# USB_Serial.net
KiCad netlist of a schematic drawn in Altium Designer
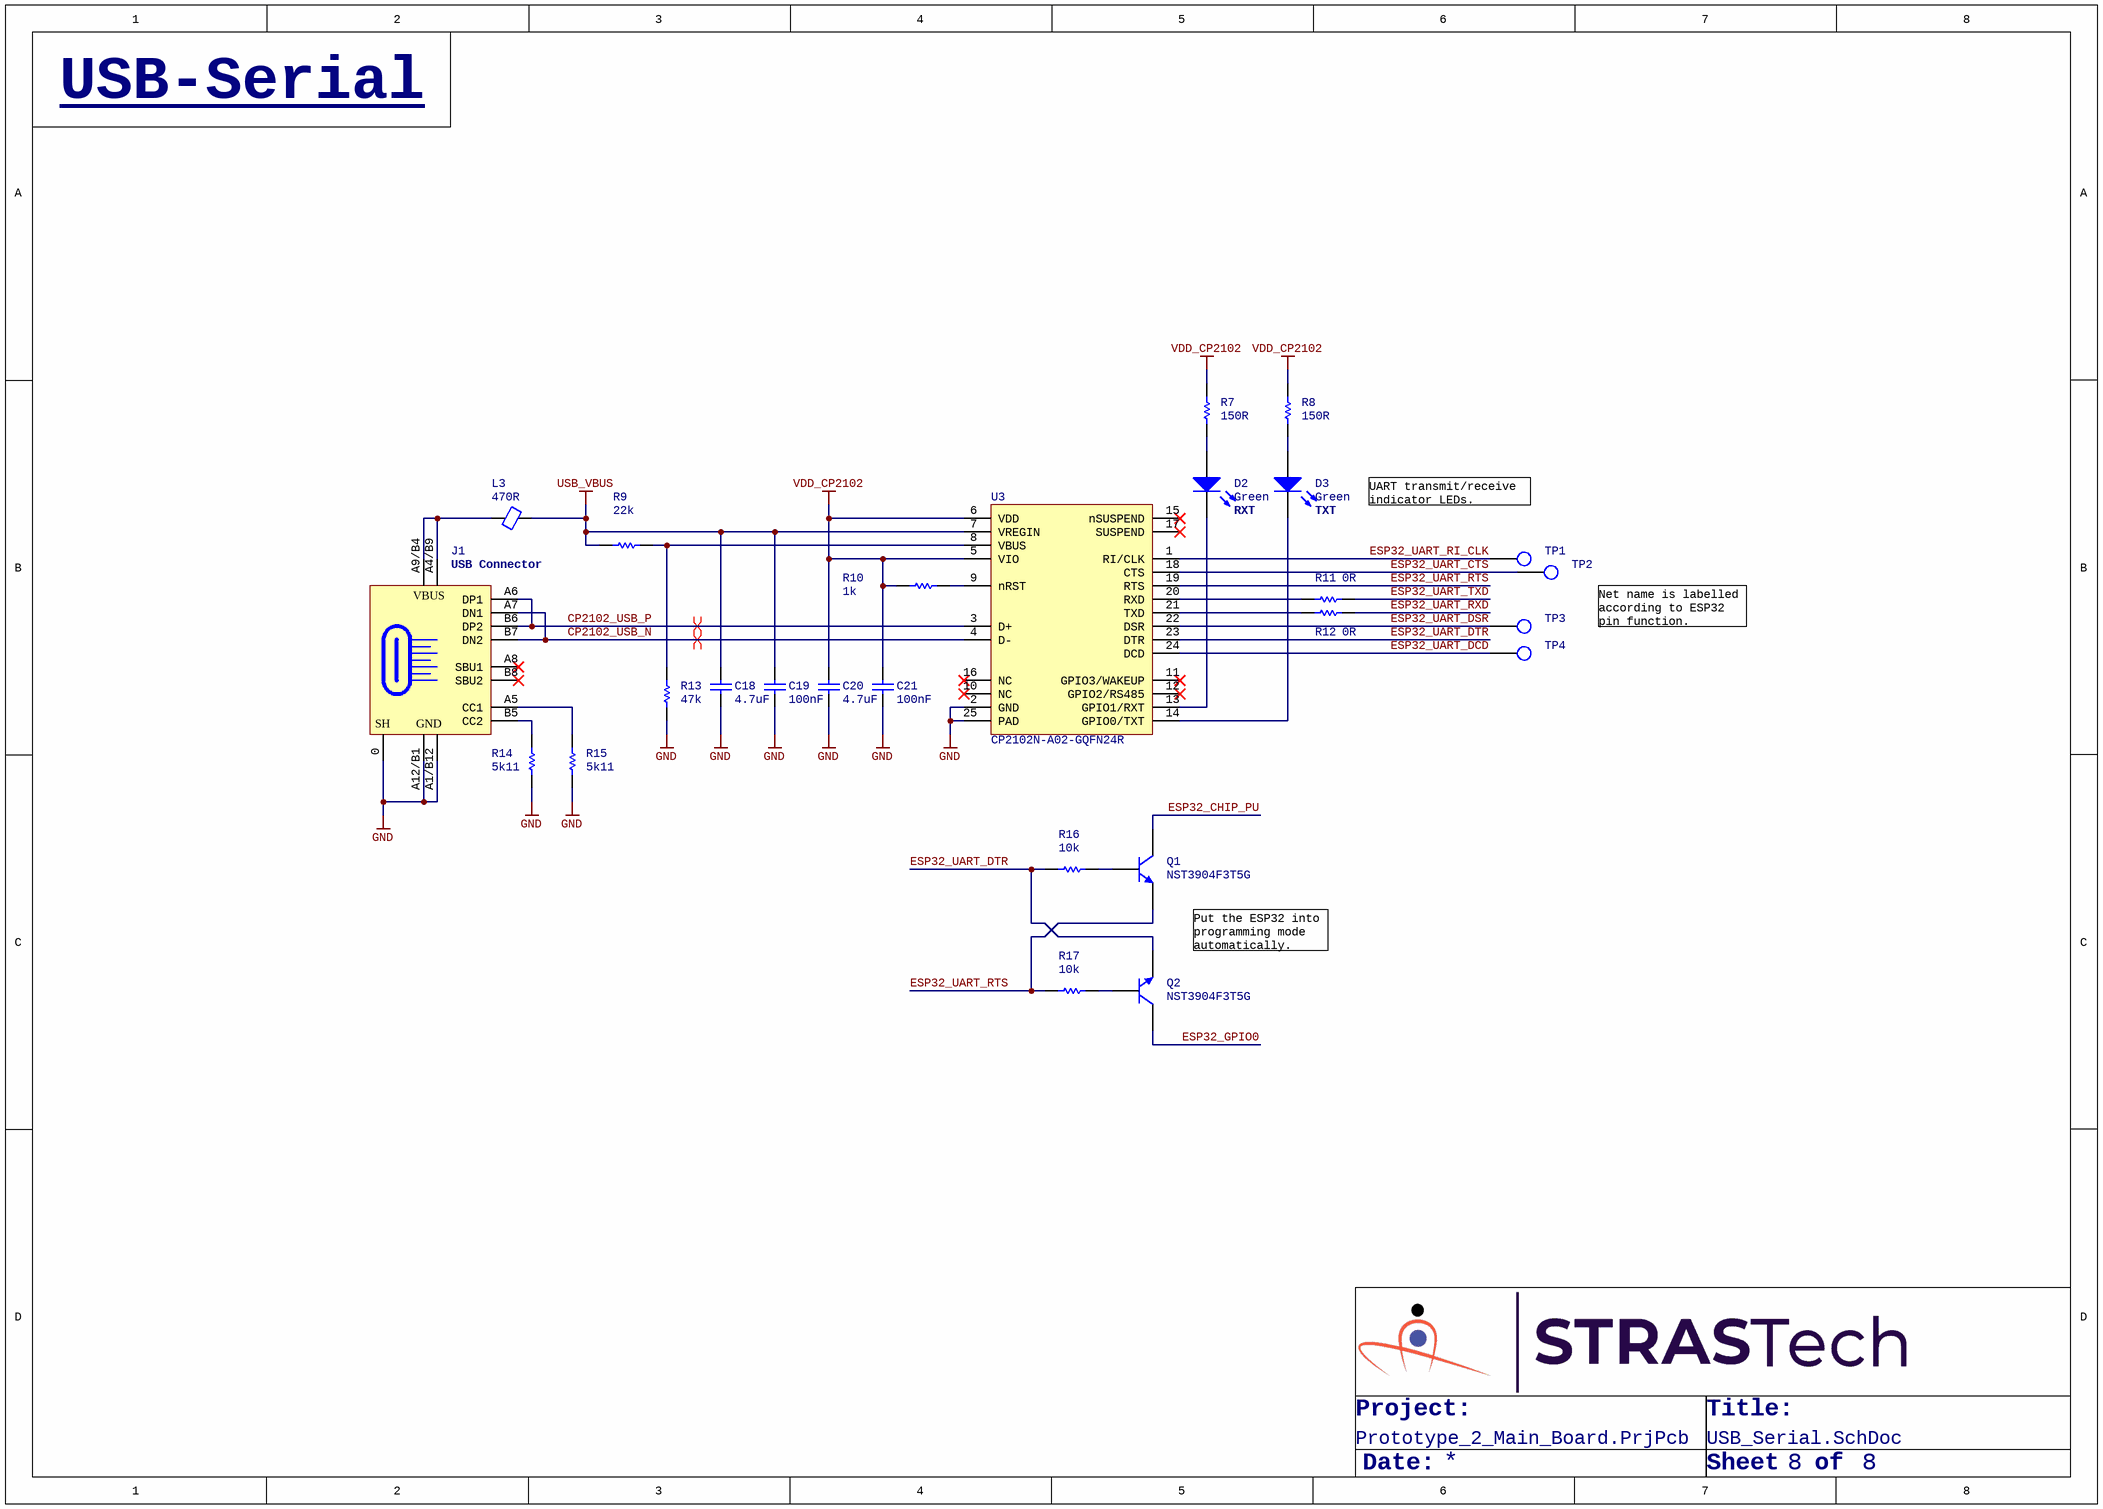
[diagram p0: USB_Serial.SchDoc]

(export (version "E")
  (design (tool "Eeschema 10.0.6"))
  (components
    (comp (ref "C18")
      (value "4.7uF")
      (footprint "Cap,SMD,0402")
      (description "4.7 µF ±20% 16V Ceramic Capacitor X5R 0402 (1005 Metric)")
      (fields
        (field (name "VENDOR PART NUMBER") "478-10788-1-ND")
        (field (name "MANUFACTURER") "AVX Corporation")
        (field (name "CREATEDBY") "Judd Foster")
      )
      (libsource (lib "symbols") (part "CAP,Cer,4.7uF,16VDC,X5R,0402"))
    )
    (comp (ref "C19")
      (value "100nF")
      (footprint "Cap,SMD,0402")
      (description "0.1µF ±10% 25V Ceramic Capacitor X7R 0402 (1005 Metric)")
      (fields
        (field (name "VENDOR PART NUMBER") "490-14603-1-ND")
        (field (name "MANUFACTURER") "Murata Electronics")
        (field (name "CREATEDBY") "Judd Foster")
      )
      (libsource (lib "symbols") (part "CAP,Cer,100nF,25VDC,X7R,0402"))
    )
    (comp (ref "C20")
      (value "4.7uF")
      (footprint "Cap,SMD,0402")
      (description "4.7 µF ±20% 16V Ceramic Capacitor X5R 0402 (1005 Metric)")
      (fields
        (field (name "VENDOR PART NUMBER") "478-10788-1-ND")
        (field (name "MANUFACTURER") "AVX Corporation")
        (field (name "CREATEDBY") "Judd Foster")
      )
      (libsource (lib "symbols") (part "CAP,Cer,4.7uF,16VDC,X5R,0402"))
    )
    (comp (ref "C21")
      (value "100nF")
      (footprint "Cap,SMD,0402")
      (description "0.1µF ±10% 25V Ceramic Capacitor X7R 0402 (1005 Metric)")
      (fields
        (field (name "VENDOR PART NUMBER") "490-14603-1-ND")
        (field (name "MANUFACTURER") "Murata Electronics")
        (field (name "CREATEDBY") "Judd Foster")
      )
      (libsource (lib "symbols") (part "CAP,Cer,100nF,25VDC,X7R,0402"))
    )
    (comp (ref "D2")
      (value "Green")
      (footprint "LED,0603")
      (description "Green 530nm LED Indication - Discrete 3V 0603 (1608 Metric)")
      (fields
        (field (name "MANUFACTURER") "Stanley Electric Co")
        (field (name "MANUFACTURER PART NUMBER") "THG1111C-0005-TR")
        (field (name "CREATEDBY") "Judd Foster")
      )
      (libsource (lib "symbols") (part "LED,Green,SMD,0603"))
    )
    (comp (ref "D3")
      (value "Green")
      (footprint "LED,0603")
      (description "Green 530nm LED Indication - Discrete 3V 0603 (1608 Metric)")
      (fields
        (field (name "MANUFACTURER") "Stanley Electric Co")
        (field (name "MANUFACTURER PART NUMBER") "THG1111C-0005-TR")
        (field (name "CREATEDBY") "Judd Foster")
      )
      (libsource (lib "symbols") (part "LED,Green,SMD,0603"))
    )
    (comp (ref "J1")
      (value "USB")
      (footprint "CONN,USB_C,SMD")
      (fields
        (field (name "MANUFACTURER") "GCT")
        (field (name "MANUFACTURER PART NUMBER") "USB4110-GF-A")
        (field (name "VENDOR PART NUMBER") "2073-USB4110-GF-A-1-ND")
        (field (name "CREATEDBY") "Judd Foster")
      )
      (libsource (lib "symbols") (part "Conn,USB_C,SMD"))
    )
    (comp (ref "L3")
      (value "470R")
      (footprint "IND,0402")
      (description "470 Ohms @ 100 MHz 1 Power Line Ferrite Bead 0402 (1005 Metric) 1A 200mOhm")
      (fields
        (field (name "VENDOR PART NUMBER") "490-10662-1-ND")
        (field (name "MANUFACTURER") "Murata Electronics")
        (field (name "CREATEDBY") "Judd Foster")
      )
      (libsource (lib "symbols") (part "Ferrite,470R@100MHz,0402"))
    )
    (comp (ref "Q1")
      (value "NST3904F3T5G")
      (footprint "SOT1123")
      (description "Bipolar (BJT) Transistor NPN 40 V 200 mA 200MHz 290 mW Surface Mount SOT-1123")
      (fields
        (field (name "MANUFACTURER") "ON Semiconductor")
        (field (name "VENDOR PART NUMBER") "NST3904F3T5GOSCT-ND")
        (field (name "CREATEDBY") "Judd Foster")
      )
      (libsource (lib "symbols") (part "Trans,NPN,40V,200mA,SOT1123"))
    )
    (comp (ref "Q2")
      (value "NST3904F3T5G")
      (footprint "SOT1123")
      (description "Bipolar (BJT) Transistor NPN 40 V 200 mA 200MHz 290 mW Surface Mount SOT-1123")
      (fields
        (field (name "MANUFACTURER") "ON Semiconductor")
        (field (name "VENDOR PART NUMBER") "NST3904F3T5GOSCT-ND")
        (field (name "CREATEDBY") "Judd Foster")
      )
      (libsource (lib "symbols") (part "Trans,NPN,40V,200mA,SOT1123"))
    )
    (comp (ref "R7")
      (value "150R")
      (footprint "RES,0402")
      (fields
        (field (name "MANUFACTURER") "TE Connectivity Passive Product")
        (field (name "MANUFACTURER PART NUMBER") "CRGCQ0402F150R")
        (field (name "VENDOR PART NUMBER") "A129617CT-ND")
        (field (name "CREATEDBY") "Judd Foster")
      )
      (libsource (lib "symbols") (part "RES,150R,1%,0.1W,0402"))
    )
    (comp (ref "R8")
      (value "150R")
      (footprint "RES,0402")
      (fields
        (field (name "MANUFACTURER") "TE Connectivity Passive Product")
        (field (name "MANUFACTURER PART NUMBER") "CRGCQ0402F150R")
        (field (name "VENDOR PART NUMBER") "A129617CT-ND")
        (field (name "CREATEDBY") "Judd Foster")
      )
      (libsource (lib "symbols") (part "RES,150R,1%,0.1W,0402"))
    )
    (comp (ref "R9")
      (value "22k")
      (footprint "RES,0402")
      (description "22 kOhms ±1% 0.063W, 1/16W Chip Resistor 0402 (1005 Metric) Automotive AEC-Q200 Thick Film")
      (fields
        (field (name "VENDOR PART NUMBER") "RMCF0402FT22K0CT-ND")
        (field (name "MANUFACTURER") "Stackpole Electronics Inc")
        (field (name "CREATEDBY") "Judd Foster")
      )
      (libsource (lib "symbols") (part "RES,22k,1%,0.063W,0402"))
    )
    (comp (ref "R10")
      (value "1k")
      (footprint "RES,0402")
      (description "1 kOhms ±5% 0.063W, 1/16W Chip Resistor 0402 (1005 Metric) Automotive AEC-Q200 Thick Film")
      (fields
        (field (name "VENDOR PART NUMBER") "RMCF0402JT1K00CT-ND")
        (field (name "MANUFACTURER") "Stackpole Electronics Inc")
        (field (name "CREATEDBY") "Judd Foster")
      )
      (libsource (lib "symbols") (part "RES,1k,5%,0.063W,0402"))
    )
    (comp (ref "R11")
      (value "0R")
      (footprint "RES,0402")
      (description "0 Ohms Jumper 0.1W, 1/10W Chip Resistor 0402 (1005 Metric) Automotive AEC-Q200 Thick Film")
      (fields
        (field (name "MANUFACTURER") "Panasonic Electronic Components")
        (field (name "MANUFACTURER PART NUMBER") "ERJ-2GE0R00X")
        (field (name "CREATEDBY") "Judd Foster")
      )
      (libsource (lib "symbols") (part "RES,0R0,0.1W,0402"))
    )
    (comp (ref "R12")
      (value "0R")
      (footprint "RES,0402")
      (description "0 Ohms Jumper 0.1W, 1/10W Chip Resistor 0402 (1005 Metric) Automotive AEC-Q200 Thick Film")
      (fields
        (field (name "MANUFACTURER") "Panasonic Electronic Components")
        (field (name "MANUFACTURER PART NUMBER") "ERJ-2GE0R00X")
        (field (name "CREATEDBY") "Judd Foster")
      )
      (libsource (lib "symbols") (part "RES,0R0,0.1W,0402"))
    )
    (comp (ref "R13")
      (value "47k")
      (footprint "RES,0402")
      (description "47 kOhms ±1% 0.1W, 1/10W Chip Resistor 0402 (1005 Metric) Automotive AEC-Q200 Thick Film")
      (fields
        (field (name "MANUFACTURER") "Panasonic Electronic Components")
        (field (name "MANUFACTURER PART NUMBER") "ERJ-2RKF4702X")
        (field (name "CREATEDBY") "Judd Foster")
      )
      (libsource (lib "symbols") (part "RES,47k,1%,0.1W,0402"))
    )
    (comp (ref "R14")
      (value "5k11")
      (footprint "RES,0402")
      (fields
        (field (name "MANUFACTURER") "Yageo")
        (field (name "MANUFACTURER PART NUMBER") "AC0402FR-075K11L")
        (field (name "VENDOR PART NUMBER") "13-AC0402FR-075K11LCT-ND")
        (field (name "CREATEDBY") "Judd Foster")
      )
      (libsource (lib "symbols") (part "RES,5k11,1%,0.063W,0402"))
    )
    (comp (ref "R15")
      (value "5k11")
      (footprint "RES,0402")
      (fields
        (field (name "MANUFACTURER") "Yageo")
        (field (name "MANUFACTURER PART NUMBER") "AC0402FR-075K11L")
        (field (name "VENDOR PART NUMBER") "13-AC0402FR-075K11LCT-ND")
        (field (name "CREATEDBY") "Judd Foster")
      )
      (libsource (lib "symbols") (part "RES,5k11,1%,0.063W,0402"))
    )
    (comp (ref "R16")
      (value "10k")
      (footprint "RES,0402")
      (description "10 kOhms ±5% 0.063W, 1/16W Chip Resistor 0402 (1005 Metric) Automotive AEC-Q200 Thick Film")
      (fields
        (field (name "VENDOR PART NUMBER") "RMCF0402JT10K0CT-ND")
        (field (name "MANUFACTURER") "Stackpole Electronics Inc")
        (field (name "CREATEDBY") "Judd Foster")
      )
      (libsource (lib "symbols") (part "RES,10k,5%,0.063W,0402"))
    )
    (comp (ref "R17")
      (value "10k")
      (footprint "RES,0402")
      (description "10 kOhms ±5% 0.063W, 1/16W Chip Resistor 0402 (1005 Metric) Automotive AEC-Q200 Thick Film")
      (fields
        (field (name "VENDOR PART NUMBER") "RMCF0402JT10K0CT-ND")
        (field (name "MANUFACTURER") "Stackpole Electronics Inc")
        (field (name "CREATEDBY") "Judd Foster")
      )
      (libsource (lib "symbols") (part "RES,10k,5%,0.063W,0402"))
    )
    (comp (ref "TP1")
      (value "TESTPOINT")
      (footprint "testpoint,smd,round,1mm")
      (description "PCB Testpoint")
      (fields (field (name "CREATEDBY") "Judd Foster"))
      (libsource (lib "symbols") (part "TESTPOINT"))
    )
    (comp (ref "TP2")
      (value "TESTPOINT")
      (footprint "testpoint,smd,round,1mm")
      (description "PCB Testpoint")
      (fields (field (name "CREATEDBY") "Judd Foster"))
      (libsource (lib "symbols") (part "TESTPOINT"))
    )
    (comp (ref "TP3")
      (value "TESTPOINT")
      (footprint "testpoint,smd,round,1mm")
      (description "PCB Testpoint")
      (fields (field (name "CREATEDBY") "Judd Foster"))
      (libsource (lib "symbols") (part "TESTPOINT"))
    )
    (comp (ref "TP4")
      (value "TESTPOINT")
      (footprint "testpoint,smd,round,1mm")
      (description "PCB Testpoint")
      (fields (field (name "CREATEDBY") "Judd Foster"))
      (libsource (lib "symbols") (part "TESTPOINT"))
    )
    (comp (ref "U3")
      (value "CP2102N-A02-GQFN24R")
      (footprint "IC,VQFN-24,THERMAL,4x4")
      (description "USB Bridge, USB to UART USB 2.0 UART Interface 24-QFN (4x4)")
      (fields
        (field (name "MANUFACTURER") "Silicon Labs")
        (field (name "VENDOR PART NUMBER") "336-5888-1-ND")
        (field (name "CREATEDBY") "Judd Foster")
      )
      (libsource (lib "symbols") (part "CP2102N-A02-GQFN24R"))
    )
  )
  (nets
    (net (code "1") (name "/CP2102_USB_N") (class "Default")
      (node (ref "J1") (pin "A7") (pinfunction "DN1_A7") (pintype "passive"))
      (node (ref "J1") (pin "B7") (pinfunction "DN2_B7") (pintype "passive"))
      (node (ref "U3") (pin "4") (pinfunction "D-_4") (pintype "passive"))
    )
    (net (code "2") (name "/CP2102_USB_P") (class "Default")
      (node (ref "J1") (pin "A6") (pinfunction "DP1_A6") (pintype "passive"))
      (node (ref "J1") (pin "B6") (pinfunction "DP2_B6") (pintype "passive"))
      (node (ref "U3") (pin "3") (pinfunction "D+_3") (pintype "passive"))
    )
    (net (code "3") (name "/ESP32_CHIP_PU") (class "Default")
      (node (ref "Q1") (pin "3") (pinfunction "C_3") (pintype "passive"))
    )
    (net (code "4") (name "/ESP32_GPIO0") (class "Default")
      (node (ref "Q2") (pin "3") (pinfunction "C_3") (pintype "passive"))
    )
    (net (code "5") (name "/ESP32_UART_CTS") (class "Default")
      (node (ref "TP2") (pin "1") (pinfunction "TP_1") (pintype "passive"))
      (node (ref "U3") (pin "18") (pinfunction "CTS_18") (pintype "passive"))
    )
    (net (code "6") (name "/ESP32_UART_DCD") (class "Default")
      (node (ref "TP4") (pin "1") (pinfunction "TP_1") (pintype "passive"))
      (node (ref "U3") (pin "24") (pinfunction "DCD_24") (pintype "passive"))
    )
    (net (code "7") (name "/ESP32_UART_DSR") (class "Default")
      (node (ref "TP3") (pin "1") (pinfunction "TP_1") (pintype "passive"))
      (node (ref "U3") (pin "22") (pinfunction "DSR_22") (pintype "passive"))
    )
    (net (code "8") (name "/ESP32_UART_DTR") (class "Default")
      (node (ref "Q2") (pin "2") (pinfunction "E_2") (pintype "passive"))
      (node (ref "R16") (pin "2") (pinfunction "2_2") (pintype "passive"))
      (node (ref "U3") (pin "23") (pinfunction "DTR_23") (pintype "passive"))
    )
    (net (code "9") (name "/ESP32_UART_RI_CLK") (class "Default")
      (node (ref "TP1") (pin "1") (pinfunction "TP_1") (pintype "passive"))
      (node (ref "U3") (pin "1") (pinfunction "RI/CLK_1") (pintype "passive"))
    )
    (net (code "10") (name "/ESP32_UART_RTS") (class "Default")
      (node (ref "Q1") (pin "2") (pinfunction "E_2") (pintype "passive"))
      (node (ref "R17") (pin "2") (pinfunction "2_2") (pintype "passive"))
      (node (ref "U3") (pin "19") (pinfunction "RTS_19") (pintype "passive"))
    )
    (net (code "11") (name "/ESP32_UART_RXD") (class "Default")
      (node (ref "R12") (pin "2") (pinfunction "2_2") (pintype "passive"))
    )
    (net (code "12") (name "/ESP32_UART_TXD") (class "Default")
      (node (ref "R11") (pin "2") (pinfunction "2_2") (pintype "passive"))
    )
    (net (code "13") (name "GND") (class "Default")
      (node (ref "C18") (pin "1") (pinfunction "1_1") (pintype "passive"))
      (node (ref "C19") (pin "1") (pinfunction "1_1") (pintype "passive"))
      (node (ref "C20") (pin "1") (pinfunction "1_1") (pintype "passive"))
      (node (ref "C21") (pin "1") (pinfunction "1_1") (pintype "passive"))
      (node (ref "J1") (pin "0") (pinfunction "SHIELD_0") (pintype "passive"))
      (node (ref "J1") (pin "A1/B12") (pinfunction "GND_A1/B12") (pintype "passive"))
      (node (ref "J1") (pin "A12/B1") (pinfunction "GND_A12/B1") (pintype "passive"))
      (node (ref "R13") (pin "1") (pinfunction "1_1") (pintype "passive"))
      (node (ref "R14") (pin "1") (pinfunction "1_1") (pintype "passive"))
      (node (ref "R15") (pin "1") (pinfunction "1_1") (pintype "passive"))
      (node (ref "U3") (pin "2") (pinfunction "GND_2") (pintype "passive"))
      (node (ref "U3") (pin "25") (pinfunction "PAD_25") (pintype "passive"))
    )
    (net (code "14") (name "Net-(D2-A)") (class "Default")
      (node (ref "D2") (pin "1") (pinfunction "A_1") (pintype "passive"))
      (node (ref "R7") (pin "1") (pinfunction "1_1") (pintype "passive"))
    )
    (net (code "15") (name "Net-(D2-K)") (class "Default")
      (node (ref "D2") (pin "2") (pinfunction "K_2") (pintype "passive"))
      (node (ref "U3") (pin "13") (pinfunction "GPIO1/RXT_13") (pintype "passive"))
    )
    (net (code "16") (name "Net-(D3-A)") (class "Default")
      (node (ref "D3") (pin "1") (pinfunction "A_1") (pintype "passive"))
      (node (ref "R8") (pin "1") (pinfunction "1_1") (pintype "passive"))
    )
    (net (code "17") (name "Net-(D3-K)") (class "Default")
      (node (ref "D3") (pin "2") (pinfunction "K_2") (pintype "passive"))
      (node (ref "U3") (pin "14") (pinfunction "GPIO0/TXT_14") (pintype "passive"))
    )
    (net (code "18") (name "Net-(J1-CC1)") (class "Default")
      (node (ref "J1") (pin "A5") (pinfunction "CC1_A5") (pintype "passive"))
      (node (ref "R15") (pin "2") (pinfunction "2_2") (pintype "passive"))
    )
    (net (code "19") (name "Net-(J1-CC2)") (class "Default")
      (node (ref "J1") (pin "B5") (pinfunction "CC2_B5") (pintype "passive"))
      (node (ref "R14") (pin "2") (pinfunction "2_2") (pintype "passive"))
    )
    (net (code "20") (name "Net-(J1-VBUS-PadA4{slash}B9)") (class "Default")
      (node (ref "J1") (pin "A4/B9") (pinfunction "VBUS_A4/B9") (pintype "passive"))
      (node (ref "J1") (pin "A9/B4") (pinfunction "VBUS_A9/B4") (pintype "passive"))
      (node (ref "L3") (pin "1") (pinfunction "1_1") (pintype "passive"))
    )
    (net (code "21") (name "Net-(Q1-B)") (class "Default")
      (node (ref "Q1") (pin "1") (pinfunction "B_1") (pintype "passive"))
      (node (ref "R16") (pin "1") (pinfunction "1_1") (pintype "passive"))
    )
    (net (code "22") (name "Net-(Q2-B)") (class "Default")
      (node (ref "Q2") (pin "1") (pinfunction "B_1") (pintype "passive"))
      (node (ref "R17") (pin "1") (pinfunction "1_1") (pintype "passive"))
    )
    (net (code "23") (name "Net-(U3-RXD)") (class "Default")
      (node (ref "R11") (pin "1") (pinfunction "1_1") (pintype "passive"))
      (node (ref "U3") (pin "20") (pinfunction "RXD_20") (pintype "passive"))
    )
    (net (code "24") (name "Net-(U3-TXD)") (class "Default")
      (node (ref "R12") (pin "1") (pinfunction "1_1") (pintype "passive"))
      (node (ref "U3") (pin "21") (pinfunction "TXD_21") (pintype "passive"))
    )
    (net (code "25") (name "Net-(U3-VBUS)") (class "Default")
      (node (ref "R13") (pin "2") (pinfunction "2_2") (pintype "passive"))
      (node (ref "R9") (pin "2") (pinfunction "2_2") (pintype "passive"))
      (node (ref "U3") (pin "8") (pinfunction "VBUS_8") (pintype "passive"))
    )
    (net (code "26") (name "Net-(U3-nRST)") (class "Default")
      (node (ref "R10") (pin "1") (pinfunction "1_1") (pintype "passive"))
      (node (ref "U3") (pin "9") (pinfunction "nRST_9") (pintype "passive"))
    )
    (net (code "27") (name "USB_VBUS") (class "Default")
      (node (ref "C18") (pin "2") (pinfunction "2_2") (pintype "passive"))
      (node (ref "C19") (pin "2") (pinfunction "2_2") (pintype "passive"))
      (node (ref "L3") (pin "2") (pinfunction "2_2") (pintype "passive"))
      (node (ref "R9") (pin "1") (pinfunction "1_1") (pintype "passive"))
      (node (ref "U3") (pin "7") (pinfunction "VREGIN_7") (pintype "passive"))
    )
    (net (code "28") (name "VDD_CP2102") (class "Default")
      (node (ref "C20") (pin "2") (pinfunction "2_2") (pintype "passive"))
      (node (ref "C21") (pin "2") (pinfunction "2_2") (pintype "passive"))
      (node (ref "R10") (pin "2") (pinfunction "2_2") (pintype "passive"))
      (node (ref "R7") (pin "2") (pinfunction "2_2") (pintype "passive"))
      (node (ref "R8") (pin "2") (pinfunction "2_2") (pintype "passive"))
      (node (ref "U3") (pin "5") (pinfunction "VIO_5") (pintype "passive"))
      (node (ref "U3") (pin "6") (pinfunction "VDD_6") (pintype "passive"))
    )
    (net (code "29") (name "unconnected-(J1-SBU1-PadA8)") (class "Default")
      (node (ref "J1") (pin "A8") (pinfunction "SBU1_A8") (pintype "passive+no_connect"))
    )
    (net (code "30") (name "unconnected-(J1-SBU2-PadB8)") (class "Default")
      (node (ref "J1") (pin "B8") (pinfunction "SBU2_B8") (pintype "passive+no_connect"))
    )
    (net (code "31") (name "unconnected-(U3-GPIO2{slash}RS485-Pad12)") (class "Default")
      (node (ref "U3") (pin "12") (pinfunction "GPIO2/RS485_12") (pintype "passive+no_connect"))
    )
    (net (code "32") (name "unconnected-(U3-GPIO3{slash}WAKEUP-Pad11)") (class "Default")
      (node (ref "U3") (pin "11") (pinfunction "GPIO3/WAKEUP_11") (pintype "passive+no_connect"))
    )
    (net (code "33") (name "unconnected-(U3-NC-Pad10)") (class "Default")
      (node (ref "U3") (pin "10") (pinfunction "NC_10") (pintype "passive+no_connect"))
    )
    (net (code "34") (name "unconnected-(U3-NC-Pad16)") (class "Default")
      (node (ref "U3") (pin "16") (pinfunction "NC_16") (pintype "passive+no_connect"))
    )
    (net (code "35") (name "unconnected-(U3-SUSPEND-Pad17)") (class "Default")
      (node (ref "U3") (pin "17") (pinfunction "SUSPEND_17") (pintype "passive+no_connect"))
    )
    (net (code "36") (name "unconnected-(U3-nSUSPEND-Pad15)") (class "Default")
      (node (ref "U3") (pin "15") (pinfunction "nSUSPEND_15") (pintype "passive+no_connect"))
    )
  )
)
